# M6-Buck_15V.net
KiCad netlist of a schematic drawn in Altium Designer
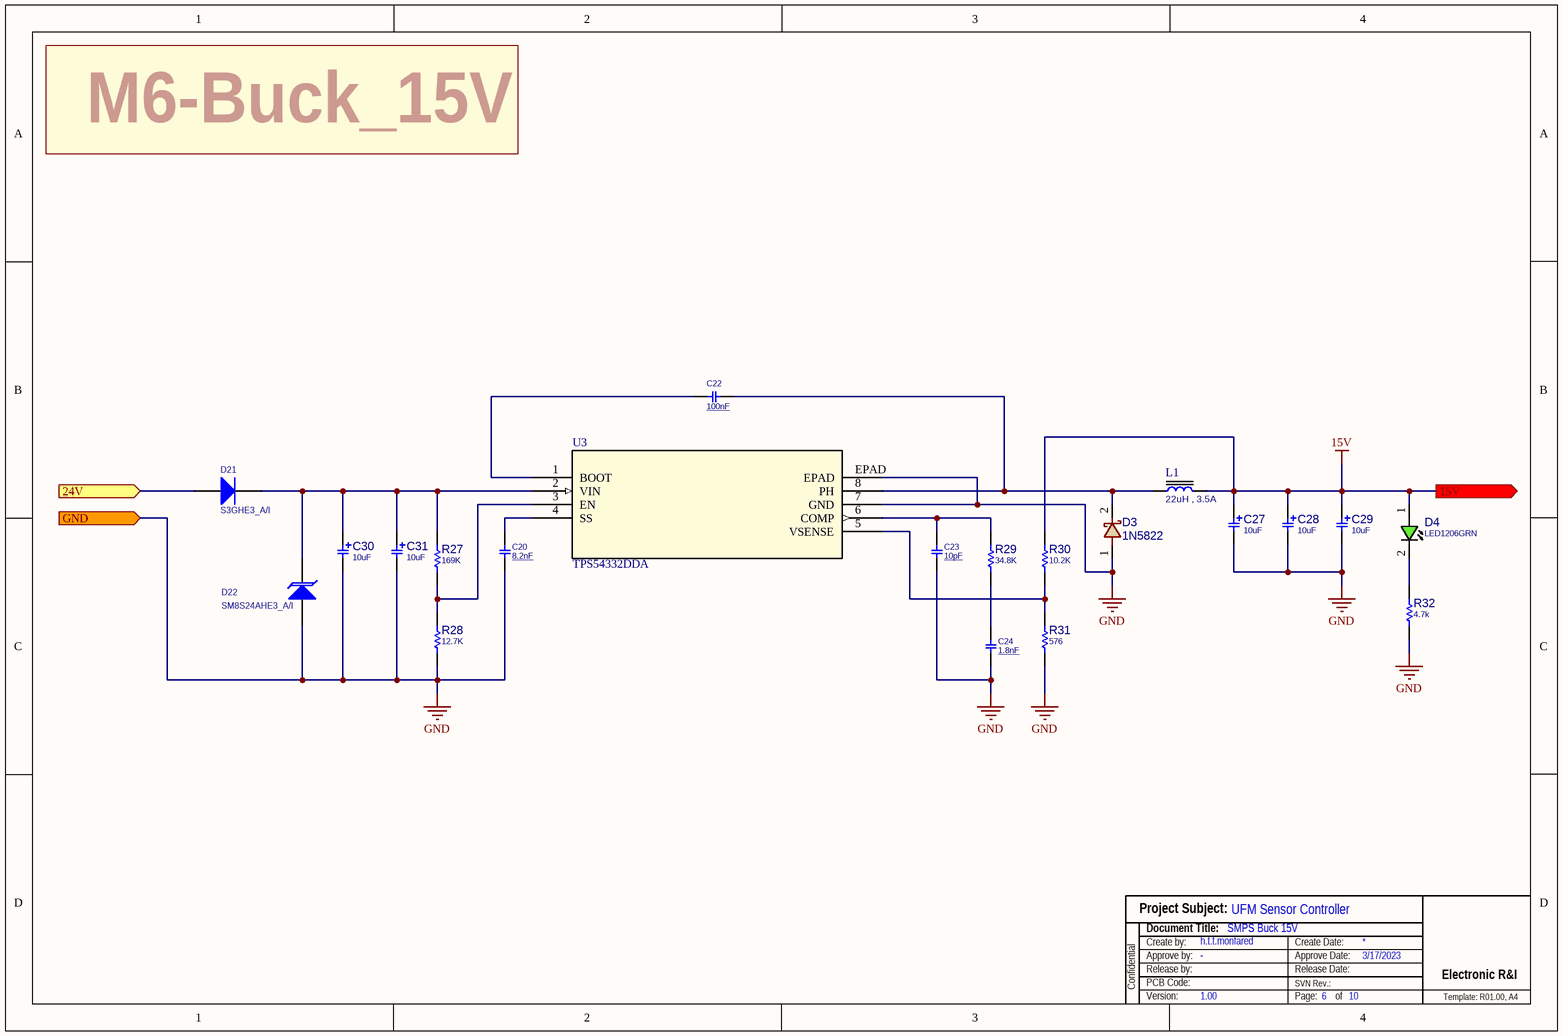
[diagram p0: M6-Buck_15V.SchDoc]

(export (version "E")
  (design (tool "Eeschema 10.0.6"))
  (components
    (comp (ref "C20")
      (value "8.2nF")
      (footprint "C1206")
      (description "CAP, MLCC, 1nF, 50V, C0G, 10%, 0402")
      (fields (field (name "MANF_P#") "MANF_PART#") (field (name "MANF") "Murata"))
      (libsource (lib "passive") (part "CAP_SMD_MLCC"))
    )
    (comp (ref "C22")
      (value "100nF")
      (footprint "C1206")
      (description "CAP, MLCC, 1nF, 50V, C0G, 10%, 0402")
      (fields (field (name "MANF_P#") "MANF_PART#") (field (name "MANF") "Murata"))
      (libsource (lib "passive") (part "CAP_SMD_MLCC"))
    )
    (comp (ref "C23")
      (value "10pF")
      (footprint "C1206")
      (description "CAP, MLCC, 1nF, 50V, C0G, 10%, 0402")
      (fields (field (name "MANF_P#") "MANF_PART#") (field (name "MANF") "Murata"))
      (libsource (lib "passive") (part "CAP_SMD_MLCC"))
    )
    (comp (ref "C24")
      (value "1.8nF")
      (footprint "C1206")
      (description "CAP, MLCC, 1nF, 50V, C0G, 10%, 0402")
      (fields (field (name "MANF_P#") "MANF_PART#") (field (name "MANF") "Murata"))
      (libsource (lib "passive") (part "CAP_SMD_MLCC"))
    )
    (comp (ref "C27")
      (value "10uF")
      (footprint "C1206")
      (description "CAP, THD, ELEC,")
      (fields (field (name "MANF_P#") "MANF_PART#") (field (name "MANF") "MANF"))
      (libsource (lib "passive") (part "CAP_SMD_EL"))
    )
    (comp (ref "C28")
      (value "10uF")
      (footprint "C1206")
      (description "CAP, THD, ELEC,")
      (fields (field (name "MANF_P#") "MANF_PART#") (field (name "MANF") "MANF"))
      (libsource (lib "passive") (part "CAP_SMD_EL"))
    )
    (comp (ref "C29")
      (value "10uF")
      (footprint "C1206")
      (description "CAP, THD, ELEC,")
      (fields (field (name "MANF_P#") "MANF_PART#") (field (name "MANF") "MANF"))
      (libsource (lib "passive") (part "CAP_SMD_EL"))
    )
    (comp (ref "C30")
      (value "10uF")
      (footprint "C1206")
      (description "CAP, THD, ELEC,")
      (fields (field (name "MANF_P#") "MANF_PART#") (field (name "MANF") "MANF"))
      (libsource (lib "passive") (part "CAP_SMD_EL"))
    )
    (comp (ref "C31")
      (value "10uF")
      (footprint "C1206")
      (description "CAP, THD, ELEC,")
      (fields (field (name "MANF_P#") "MANF_PART#") (field (name "MANF") "MANF"))
      (libsource (lib "passive") (part "CAP_SMD_EL"))
    )
    (comp (ref "D3")
      (value "1N5822")
      (footprint "D_AX06_DO27")
      (description "DIODE, SCHOTTKY, 40V, 3A")
      (fields (field (name "MANF") "Diodes"))
      (libsource (lib "diode") (part "DIODE_THD_SCHOTTKY_1N5822"))
    )
    (comp (ref "D4")
      (value "LED1206GRN")
      (footprint "LED1206GRN")
      (description "LED, SMD, 1206, GREEN")
      (libsource (lib "led(diode)") (part "LED_SMD_1206_GRN"))
    )
    (comp (ref "D21")
      (value "S3GHE3_A/I")
      (footprint "DO214AB (SMC)")
      (description "Diode-Rectifier,S,Single,400V,3A,SMC")
      (libsource (lib "Crouse") (part "Diode"))
    )
    (comp (ref "D22")
      (value "SM8S24AHE3_A/I")
      (footprint "DO-218AB")
      (description "TVS,S,UNI,26.7V,6600W,DO218AB")
      (fields (field (name "POWER") "6600W"))
      (libsource (lib "Crouse") (part "D TVS"))
    )
    (comp (ref "L1")
      (value "22uH , 3.5A")
      (footprint "L_12")
      (description "INDUCTOR, THD")
      (libsource (lib "passive") (part "IND_THD"))
    )
    (comp (ref "R27")
      (value "169K")
      (footprint "R1206")
      (description "RESISTOR, SMD")
      (fields (field (name "MANF_P#") "RK73H1ETTP4701F") (field (name "MANF") "KOA SPEER"))
      (libsource (lib "passive") (part "RES_SMD"))
    )
    (comp (ref "R28")
      (value "12.7K")
      (footprint "R1206")
      (description "RESISTOR, SMD")
      (fields (field (name "MANF_P#") "RK73H1ETTP4701F") (field (name "MANF") "KOA SPEER"))
      (libsource (lib "passive") (part "RES_SMD"))
    )
    (comp (ref "R29")
      (value "34.8K")
      (footprint "R1206")
      (description "RESISTOR, SMD")
      (fields (field (name "MANF_P#") "RK73H1ETTP4701F") (field (name "MANF") "KOA SPEER"))
      (libsource (lib "passive") (part "RES_SMD"))
    )
    (comp (ref "R30")
      (value "10.2K")
      (footprint "R1206")
      (description "RESISTOR, SMD")
      (fields (field (name "MANF_P#") "RK73H1ETTP4701F") (field (name "MANF") "KOA SPEER"))
      (libsource (lib "passive") (part "RES_SMD"))
    )
    (comp (ref "R31")
      (value "576")
      (footprint "R1206")
      (description "RESISTOR, SMD")
      (fields (field (name "MANF_P#") "RK73H1ETTP4701F") (field (name "MANF") "KOA SPEER"))
      (libsource (lib "passive") (part "RES_SMD"))
    )
    (comp (ref "R32")
      (value "4.7k")
      (footprint "R1206")
      (description "RESISTOR, SMD")
      (fields (field (name "MANF_P#") "RK73H1ETTP4701F") (field (name "MANF") "KOA SPEER"))
      (libsource (lib "passive") (part "RES_SMD"))
    )
    (comp (ref "U3")
      (value "TPS54332DDA")
      (footprint "SO_8T")
      (description "No Description Available")
      (fields (field (name "COPYRIGHT") "Copyright (C) 2022 Ultra Librarian. All rights reserved."))
      (libsource (lib "TPS54332DDA") (part "TPS54332DDA"))
    )
  )
  (nets
    (net (code "1") (name "/24V") (class "Default")
      (node (ref "D21") (pin "1") (pinfunction "A_1") (pintype "passive"))
    )
    (net (code "2") (name "15V") (class "Default")
      (node (ref "C27") (pin "1") (pinfunction "1_1") (pintype "passive"))
      (node (ref "C28") (pin "1") (pinfunction "1_1") (pintype "passive"))
      (node (ref "C29") (pin "1") (pinfunction "1_1") (pintype "passive"))
      (node (ref "D4") (pin "1") (pinfunction "ANODE_1") (pintype "passive"))
      (node (ref "L1") (pin "2") (pinfunction "2_2") (pintype "passive"))
      (node (ref "R30") (pin "2") (pinfunction "2_2") (pintype "passive"))
    )
    (net (code "3") (name "GND") (class "Default")
      (node (ref "C20") (pin "1") (pinfunction "1_1") (pintype "passive"))
      (node (ref "C23") (pin "1") (pinfunction "1_1") (pintype "passive"))
      (node (ref "C24") (pin "1") (pinfunction "1_1") (pintype "passive"))
      (node (ref "C27") (pin "2") (pinfunction "2_2") (pintype "passive"))
      (node (ref "C28") (pin "2") (pinfunction "2_2") (pintype "passive"))
      (node (ref "C29") (pin "2") (pinfunction "2_2") (pintype "passive"))
      (node (ref "C30") (pin "2") (pinfunction "2_2") (pintype "passive"))
      (node (ref "C31") (pin "2") (pinfunction "2_2") (pintype "passive"))
      (node (ref "D22") (pin "1") (pinfunction "A_1") (pintype "passive"))
      (node (ref "D3") (pin "1") (pinfunction "A_1") (pintype "passive"))
      (node (ref "R28") (pin "1") (pinfunction "1_1") (pintype "passive"))
      (node (ref "R31") (pin "1") (pinfunction "1_1") (pintype "passive"))
      (node (ref "R32") (pin "1") (pinfunction "1_1") (pintype "passive"))
      (node (ref "U3") (pin "7") (pinfunction "GND_7") (pintype "power_in"))
      (node (ref "U3") (pin "EPAD") (pinfunction "EPAD_EPAD") (pintype "passive"))
    )
    (net (code "4") (name "Net-(C24-Pad2)") (class "Default")
      (node (ref "C24") (pin "2") (pinfunction "2_2") (pintype "passive"))
      (node (ref "R29") (pin "1") (pinfunction "1_1") (pintype "passive"))
    )
    (net (code "5") (name "Net-(D3-K)") (class "Default")
      (node (ref "C22") (pin "2") (pinfunction "2_2") (pintype "passive"))
      (node (ref "D3") (pin "2") (pinfunction "K_2") (pintype "passive"))
      (node (ref "L1") (pin "1") (pinfunction "1_1") (pintype "passive"))
      (node (ref "U3") (pin "8") (pinfunction "PH_8") (pintype "power_in"))
    )
    (net (code "6") (name "Net-(D4-CATHODE)") (class "Default")
      (node (ref "D4") (pin "2") (pinfunction "CATHODE_2") (pintype "passive"))
      (node (ref "R32") (pin "2") (pinfunction "2_2") (pintype "passive"))
    )
    (net (code "7") (name "Net-(D21-K)") (class "Default")
      (node (ref "C30") (pin "1") (pinfunction "1_1") (pintype "passive"))
      (node (ref "C31") (pin "1") (pinfunction "1_1") (pintype "passive"))
      (node (ref "D21") (pin "2") (pinfunction "K_2") (pintype "passive"))
      (node (ref "D22") (pin "2") (pinfunction "K_2") (pintype "passive"))
      (node (ref "R27") (pin "2") (pinfunction "2_2") (pintype "passive"))
      (node (ref "U3") (pin "2") (pinfunction "VIN_2") (pintype "input"))
    )
    (net (code "8") (name "Net-(U3-BOOT)") (class "Default")
      (node (ref "C22") (pin "1") (pinfunction "1_1") (pintype "passive"))
      (node (ref "U3") (pin "1") (pinfunction "BOOT_1") (pintype "passive"))
    )
    (net (code "9") (name "Net-(U3-COMP)") (class "Default")
      (node (ref "C23") (pin "2") (pinfunction "2_2") (pintype "passive"))
      (node (ref "R29") (pin "2") (pinfunction "2_2") (pintype "passive"))
      (node (ref "U3") (pin "6") (pinfunction "COMP_6") (pintype "output"))
    )
    (net (code "10") (name "Net-(U3-EN)") (class "Default")
      (node (ref "R27") (pin "1") (pinfunction "1_1") (pintype "passive"))
      (node (ref "R28") (pin "2") (pinfunction "2_2") (pintype "passive"))
      (node (ref "U3") (pin "3") (pinfunction "EN_3") (pintype "passive"))
    )
    (net (code "11") (name "Net-(U3-SS)") (class "Default")
      (node (ref "C20") (pin "2") (pinfunction "2_2") (pintype "passive"))
      (node (ref "U3") (pin "4") (pinfunction "SS_4") (pintype "passive"))
    )
    (net (code "12") (name "Net-(U3-VSENSE)") (class "Default")
      (node (ref "R30") (pin "1") (pinfunction "1_1") (pintype "passive"))
      (node (ref "R31") (pin "2") (pinfunction "2_2") (pintype "passive"))
      (node (ref "U3") (pin "5") (pinfunction "VSENSE_5") (pintype "passive"))
    )
  )
)
